# TOP.net
KiCad netlist of a schematic drawn in Altium Designer
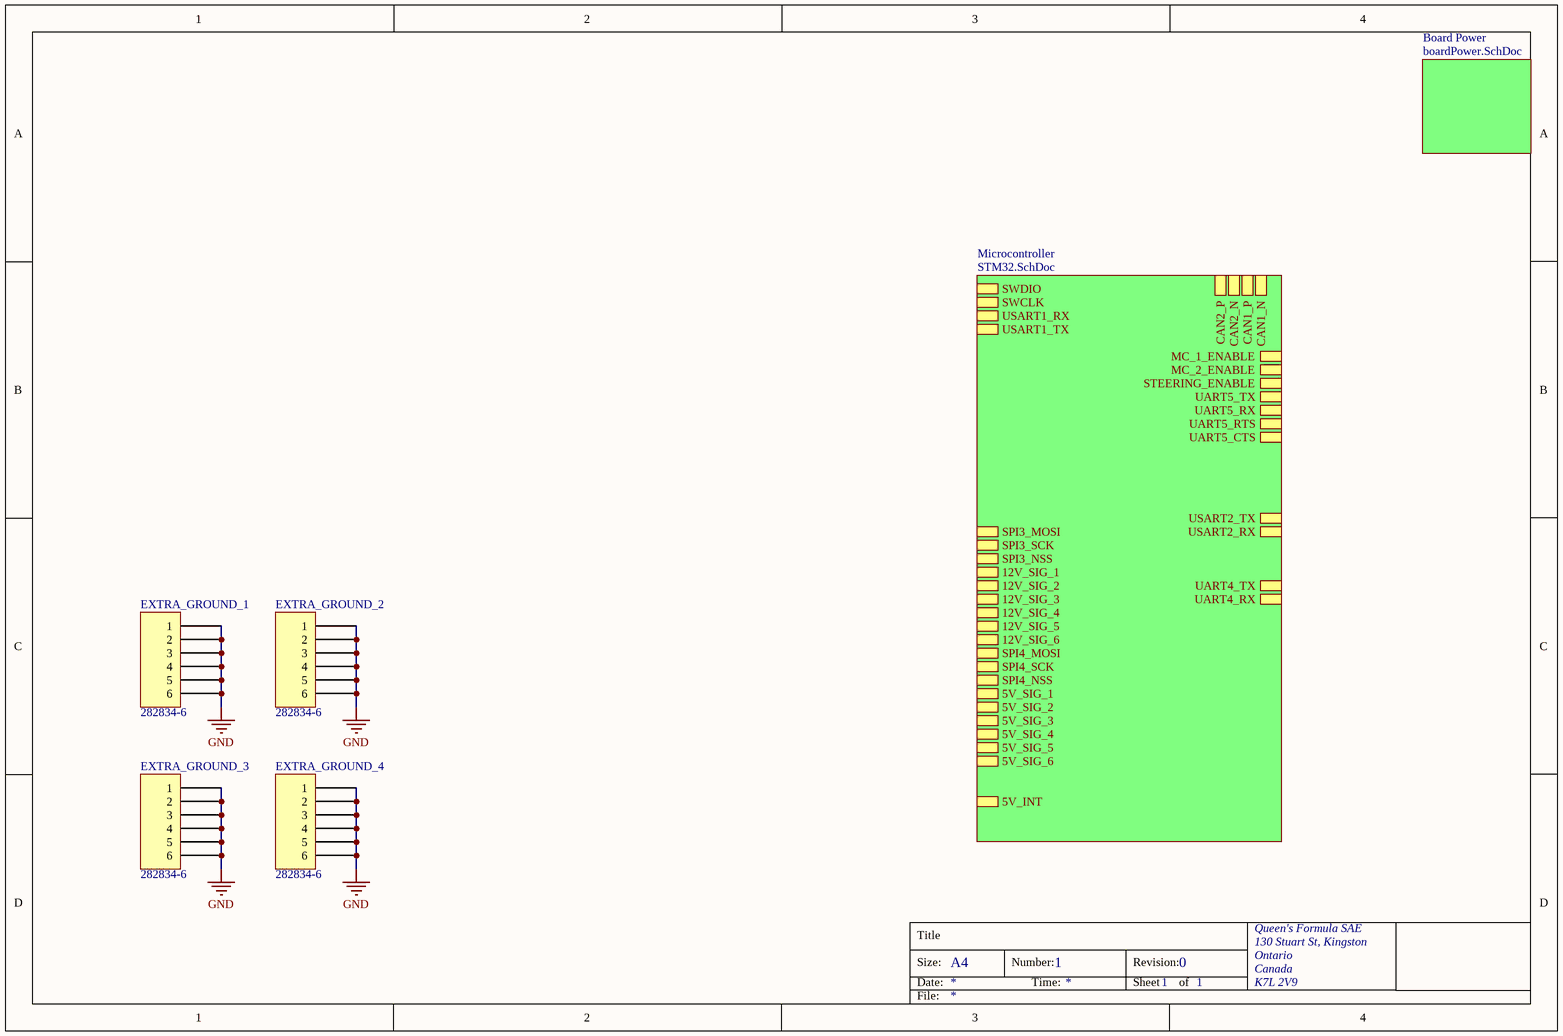
[diagram p0: TOP.SchDoc]

(export (version "E")
  (design (tool "Eeschema 10.0.6"))
  (components
    (comp (ref "EXTRA_GROUND_1")
      (value "282834-6")
      (footprint "TE 282834-6")
      (description "TERM BLK 6P SIDE ENT 2.54MM PCB")
      (fields (field (name "MANUFACTURER") "TE Connectivity AMP Connectors") (field (name "VOLTAGE") "150V"))
      (libsource (lib "Celestial Altium Library - altium_library") (part "6 Pin"))
    )
    (comp (ref "EXTRA_GROUND_2")
      (value "282834-6")
      (footprint "TE 282834-6")
      (description "TERM BLK 6P SIDE ENT 2.54MM PCB")
      (fields (field (name "MANUFACTURER") "TE Connectivity AMP Connectors") (field (name "VOLTAGE") "150V"))
      (libsource (lib "Celestial Altium Library - altium_library") (part "6 Pin"))
    )
    (comp (ref "EXTRA_GROUND_3")
      (value "282834-6")
      (footprint "TE 282834-6")
      (description "TERM BLK 6P SIDE ENT 2.54MM PCB")
      (fields (field (name "MANUFACTURER") "TE Connectivity AMP Connectors") (field (name "VOLTAGE") "150V"))
      (libsource (lib "Celestial Altium Library - altium_library") (part "6 Pin"))
    )
    (comp (ref "EXTRA_GROUND_4")
      (value "282834-6")
      (footprint "TE 282834-6")
      (description "TERM BLK 6P SIDE ENT 2.54MM PCB")
      (fields (field (name "MANUFACTURER") "TE Connectivity AMP Connectors") (field (name "VOLTAGE") "150V"))
      (libsource (lib "Celestial Altium Library - altium_library") (part "6 Pin"))
    )
  )
  (nets
    (net (code "39") (name "GND") (class "Default")
      (node (ref "EXTRA_GROUND_1") (pin "1") (pinfunction "1_1") (pintype "passive"))
      (node (ref "EXTRA_GROUND_1") (pin "2") (pinfunction "2_2") (pintype "passive"))
      (node (ref "EXTRA_GROUND_1") (pin "3") (pinfunction "3_3") (pintype "passive"))
      (node (ref "EXTRA_GROUND_1") (pin "4") (pinfunction "4_4") (pintype "passive"))
      (node (ref "EXTRA_GROUND_1") (pin "5") (pinfunction "5_5") (pintype "passive"))
      (node (ref "EXTRA_GROUND_1") (pin "6") (pinfunction "6_6") (pintype "passive"))
      (node (ref "EXTRA_GROUND_2") (pin "1") (pinfunction "1_1") (pintype "passive"))
      (node (ref "EXTRA_GROUND_2") (pin "2") (pinfunction "2_2") (pintype "passive"))
      (node (ref "EXTRA_GROUND_2") (pin "3") (pinfunction "3_3") (pintype "passive"))
      (node (ref "EXTRA_GROUND_2") (pin "4") (pinfunction "4_4") (pintype "passive"))
      (node (ref "EXTRA_GROUND_2") (pin "5") (pinfunction "5_5") (pintype "passive"))
      (node (ref "EXTRA_GROUND_2") (pin "6") (pinfunction "6_6") (pintype "passive"))
      (node (ref "EXTRA_GROUND_3") (pin "1") (pinfunction "1_1") (pintype "passive"))
      (node (ref "EXTRA_GROUND_3") (pin "2") (pinfunction "2_2") (pintype "passive"))
      (node (ref "EXTRA_GROUND_3") (pin "3") (pinfunction "3_3") (pintype "passive"))
      (node (ref "EXTRA_GROUND_3") (pin "4") (pinfunction "4_4") (pintype "passive"))
      (node (ref "EXTRA_GROUND_3") (pin "5") (pinfunction "5_5") (pintype "passive"))
      (node (ref "EXTRA_GROUND_3") (pin "6") (pinfunction "6_6") (pintype "passive"))
      (node (ref "EXTRA_GROUND_4") (pin "1") (pinfunction "1_1") (pintype "passive"))
      (node (ref "EXTRA_GROUND_4") (pin "2") (pinfunction "2_2") (pintype "passive"))
      (node (ref "EXTRA_GROUND_4") (pin "3") (pinfunction "3_3") (pintype "passive"))
      (node (ref "EXTRA_GROUND_4") (pin "4") (pinfunction "4_4") (pintype "passive"))
      (node (ref "EXTRA_GROUND_4") (pin "5") (pinfunction "5_5") (pintype "passive"))
      (node (ref "EXTRA_GROUND_4") (pin "6") (pinfunction "6_6") (pintype "passive"))
    )
  )
)
